# sistema_min.net
KiCad netlist of a schematic drawn in EAGLE
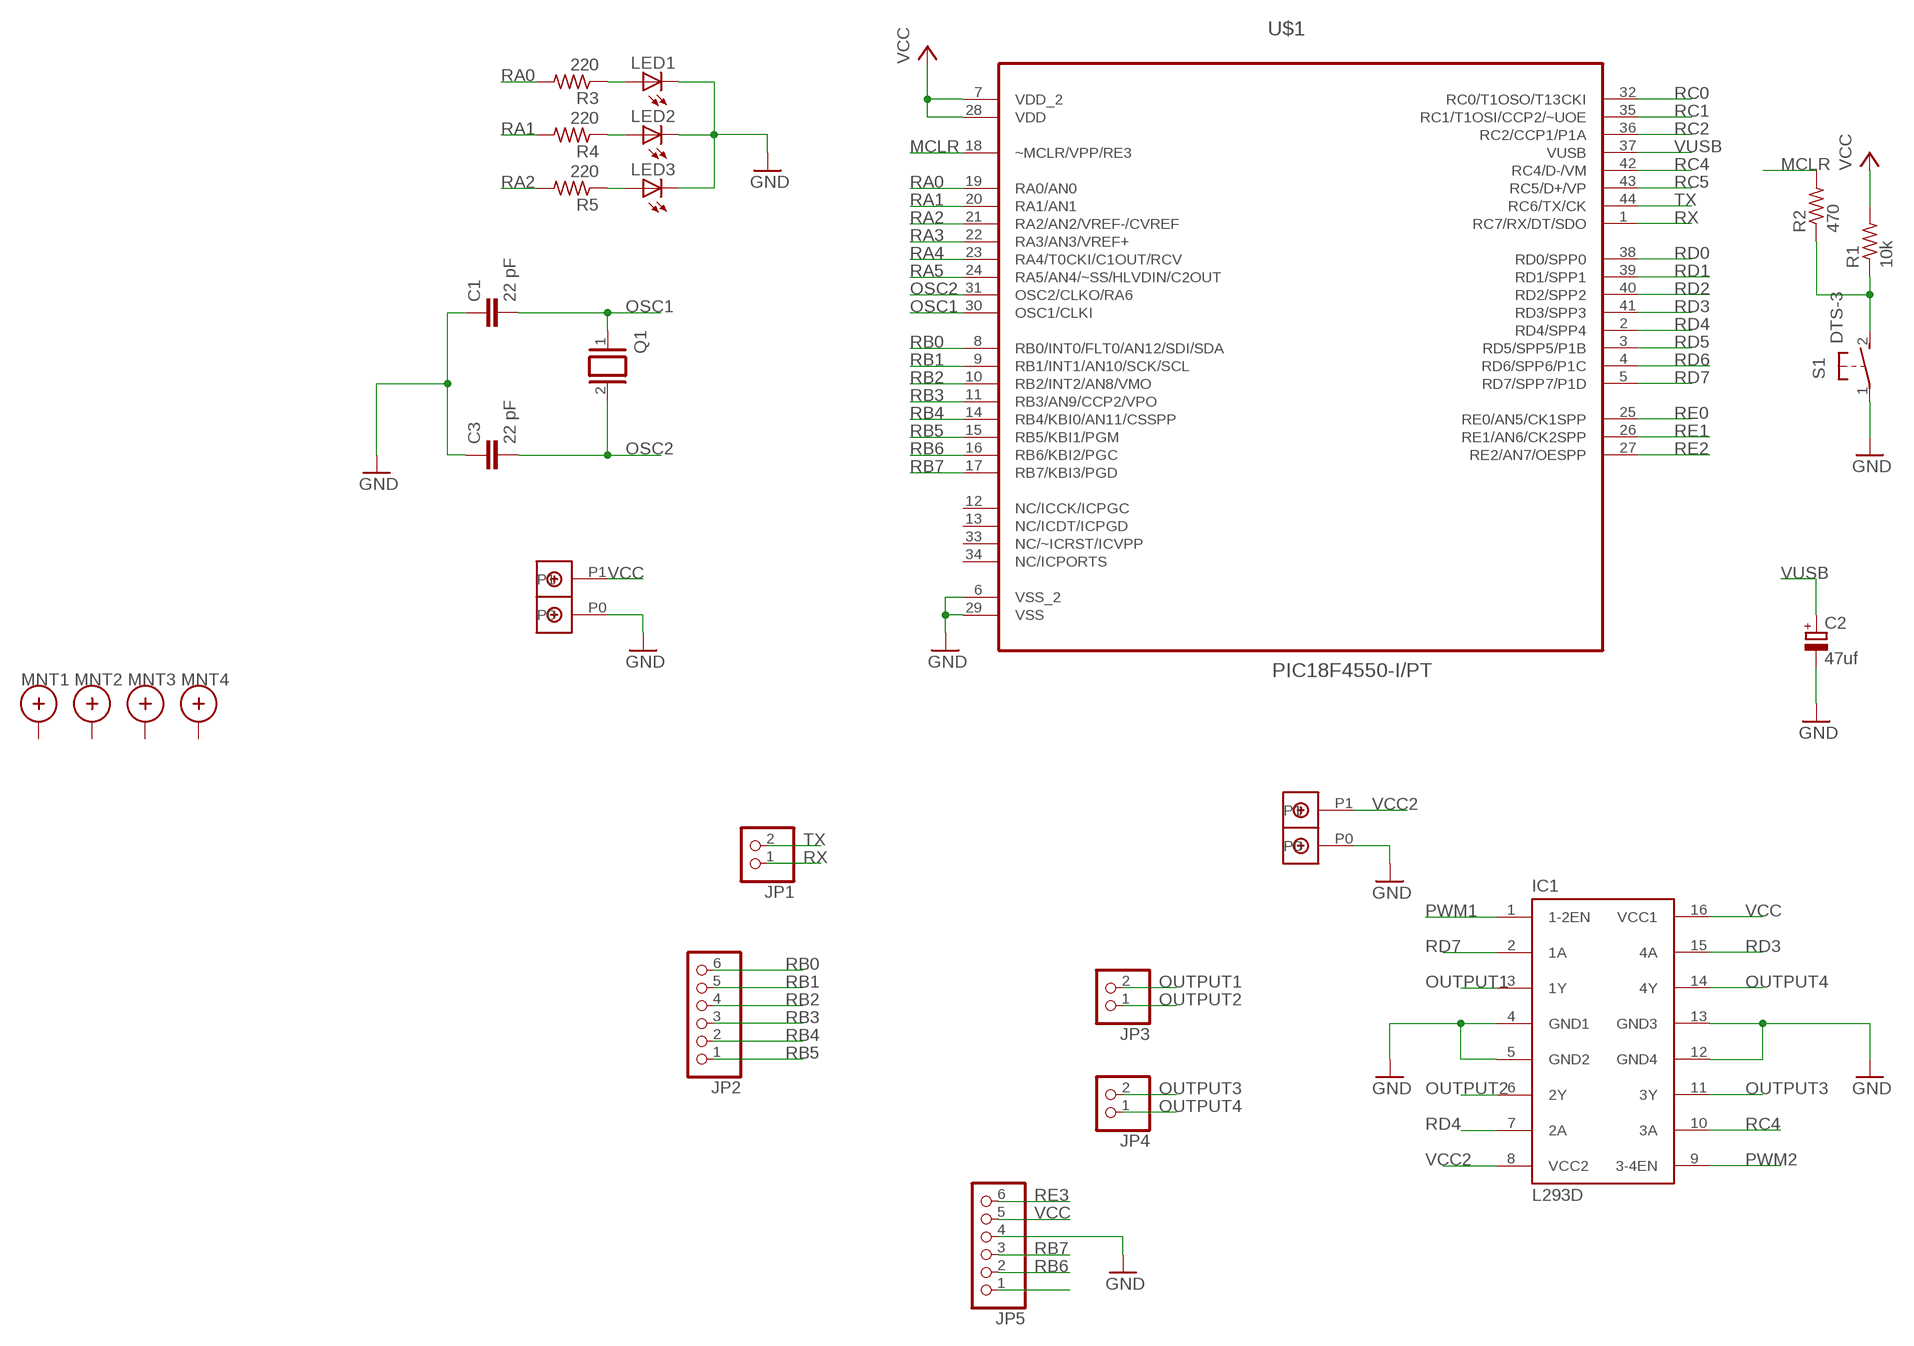
[diagram p0: schematic, sheet 1]

(export (version "E")
  (design (tool "Eeschema 10.0.6"))
  (components
    (comp (ref "C1")
      (value "22 pF")
      (footprint "eagle-import:C1206")
      (libsource (lib "eagle-import") (part "C-EUC1206"))
    )
    (comp (ref "C2")
      (value "47uf")
      (footprint "eagle-import:153CLV-0605")
      (libsource (lib "eagle-import") (part "CPOL-EU153CLV-0605"))
    )
    (comp (ref "C3")
      (value "22 pF")
      (footprint "eagle-import:C1206")
      (libsource (lib "eagle-import") (part "C-EUC1206"))
    )
    (comp (ref "IC1")
      (value "L293D")
      (footprint "eagle-import:DIL16")
      (libsource (lib "eagle-import") (part "L293D"))
    )
    (comp (ref "JP1")
      (value "PINHD-1X2")
      (footprint "eagle-import:1X02")
      (libsource (lib "eagle-import") (part "PINHD-1X2"))
    )
    (comp (ref "JP2")
      (value "PINHD-1X6")
      (footprint "eagle-import:1X06")
      (libsource (lib "eagle-import") (part "PINHD-1X6"))
    )
    (comp (ref "JP3")
      (value "PINHD-1X2")
      (footprint "eagle-import:1X02")
      (libsource (lib "eagle-import") (part "PINHD-1X2"))
    )
    (comp (ref "JP4")
      (value "PINHD-1X2")
      (footprint "eagle-import:1X02")
      (libsource (lib "eagle-import") (part "PINHD-1X2"))
    )
    (comp (ref "JP5")
      (value "PINHD-1X6")
      (footprint "eagle-import:1X06")
      (libsource (lib "eagle-import") (part "PINHD-1X6"))
    )
    (comp (ref "LED1")
      (value "LEDCHIPLED_1206")
      (footprint "eagle-import:CHIPLED_1206")
      (libsource (lib "eagle-import") (part "LEDCHIPLED_1206"))
    )
    (comp (ref "LED2")
      (value "LEDCHIPLED_1206")
      (footprint "eagle-import:CHIPLED_1206")
      (libsource (lib "eagle-import") (part "LEDCHIPLED_1206"))
    )
    (comp (ref "LED3")
      (value "LEDCHIPLED_1206")
      (footprint "eagle-import:CHIPLED_1206")
      (libsource (lib "eagle-import") (part "LEDCHIPLED_1206"))
    )
    (comp (ref "MNT1")
      (value "HOLE_MNT_0.135")
      (footprint "eagle-import:HOLE_MNT_#5-40")
      (libsource (lib "eagle-import") (part "HOLE_MNT_0.135"))
    )
    (comp (ref "MNT2")
      (value "HOLE_MNT_0.135")
      (footprint "eagle-import:HOLE_MNT_#5-40")
      (libsource (lib "eagle-import") (part "HOLE_MNT_0.135"))
    )
    (comp (ref "MNT3")
      (value "HOLE_MNT_0.135")
      (footprint "eagle-import:HOLE_MNT_#5-40")
      (libsource (lib "eagle-import") (part "HOLE_MNT_0.135"))
    )
    (comp (ref "MNT4")
      (value "HOLE_MNT_0.135")
      (footprint "eagle-import:HOLE_MNT_#5-40")
      (libsource (lib "eagle-import") (part "HOLE_MNT_0.135"))
    )
    (comp (ref "Q1")
      (value "XTAL/S")
      (footprint "eagle-import:QS")
      (libsource (lib "eagle-import") (part "XTAL/S"))
    )
    (comp (ref "R1")
      (value "10k")
      (footprint "eagle-import:M1206")
      (libsource (lib "eagle-import") (part "R-US_M1206"))
    )
    (comp (ref "R2")
      (value "470")
      (footprint "eagle-import:M1206")
      (libsource (lib "eagle-import") (part "R-US_M1206"))
    )
    (comp (ref "R3")
      (value "220")
      (footprint "eagle-import:M1206")
      (libsource (lib "eagle-import") (part "R-US_M1206"))
    )
    (comp (ref "R4")
      (value "220")
      (footprint "eagle-import:M1206")
      (libsource (lib "eagle-import") (part "R-US_M1206"))
    )
    (comp (ref "R5")
      (value "220")
      (footprint "eagle-import:M1206")
      (libsource (lib "eagle-import") (part "R-US_M1206"))
    )
    (comp (ref "S1")
      (value "DTS-3")
      (footprint "eagle-import:DTS-3")
      (libsource (lib "eagle-import") (part "DTS-3"))
    )
    (comp (ref "U$1")
      (value "PIC18F4550-I/PT")
      (footprint "eagle-import:QFP80P1200X1200X120-44N")
      (libsource (lib "eagle-import") (part "PIC18F4550-I/PT"))
    )
    (comp (ref "U$2")
      (value "DBCONN-1X2")
      (footprint "eagle-import:DBCONN-1X2")
      (libsource (lib "eagle-import") (part "DBCONN-1X2"))
    )
    (comp (ref "U$3")
      (value "DBCONN-1X2")
      (footprint "eagle-import:DBCONN-1X2")
      (libsource (lib "eagle-import") (part "DBCONN-1X2"))
    )
  )
  (nets
    (net (code "1") (name "/MCLR") (class "Default")
      (node (ref "R2") (pin "2") (pinfunction "2_2") (pintype "passive"))
      (node (ref "U$1") (pin "18") (pinfunction "~{MCLR/VPP/RE3}_18") (pintype "input"))
    )
    (net (code "2") (name "/OSC1") (class "Default")
      (node (ref "C1") (pin "2") (pinfunction "2_2") (pintype "passive"))
      (node (ref "Q1") (pin "1") (pinfunction "1_1") (pintype "passive"))
      (node (ref "U$1") (pin "30") (pinfunction "OSC1/CLKI_30") (pintype "bidirectional"))
    )
    (net (code "3") (name "/OSC2") (class "Default")
      (node (ref "C3") (pin "2") (pinfunction "2_2") (pintype "passive"))
      (node (ref "Q1") (pin "2") (pinfunction "2_2") (pintype "passive"))
      (node (ref "U$1") (pin "31") (pinfunction "OSC2/CLKO/RA6_31") (pintype "bidirectional"))
    )
    (net (code "4") (name "/OUTPUT1") (class "Default")
      (node (ref "IC1") (pin "3") (pinfunction "1Y_3") (pintype "output"))
      (node (ref "JP3") (pin "2") (pinfunction "2_2") (pintype "passive"))
    )
    (net (code "5") (name "/OUTPUT2") (class "Default")
      (node (ref "IC1") (pin "6") (pinfunction "2Y_6") (pintype "output"))
      (node (ref "JP3") (pin "1") (pinfunction "1_1") (pintype "passive"))
    )
    (net (code "6") (name "/OUTPUT3") (class "Default")
      (node (ref "IC1") (pin "11") (pinfunction "3Y_11") (pintype "output"))
      (node (ref "JP4") (pin "2") (pinfunction "2_2") (pintype "passive"))
    )
    (net (code "7") (name "/OUTPUT4") (class "Default")
      (node (ref "IC1") (pin "14") (pinfunction "4Y_14") (pintype "output"))
      (node (ref "JP4") (pin "1") (pinfunction "1_1") (pintype "passive"))
    )
    (net (code "8") (name "/PWM1") (class "Default")
      (node (ref "IC1") (pin "1") (pinfunction "1-2EN_1") (pintype "input"))
    )
    (net (code "9") (name "/PWM2") (class "Default")
      (node (ref "IC1") (pin "9") (pinfunction "3-4EN_9") (pintype "input"))
    )
    (net (code "10") (name "/RA0") (class "Default")
      (node (ref "R3") (pin "2") (pinfunction "2_2") (pintype "passive"))
      (node (ref "U$1") (pin "19") (pinfunction "RA0/AN0_19") (pintype "bidirectional"))
    )
    (net (code "11") (name "/RA1") (class "Default")
      (node (ref "R4") (pin "2") (pinfunction "2_2") (pintype "passive"))
      (node (ref "U$1") (pin "20") (pinfunction "RA1/AN1_20") (pintype "bidirectional"))
    )
    (net (code "12") (name "/RA2") (class "Default")
      (node (ref "R5") (pin "2") (pinfunction "2_2") (pintype "passive"))
      (node (ref "U$1") (pin "21") (pinfunction "RA2/AN2/VREF-/CVREF_21") (pintype "bidirectional"))
    )
    (net (code "13") (name "/RA3") (class "Default")
      (node (ref "U$1") (pin "22") (pinfunction "RA3/AN3/VREF+_22") (pintype "bidirectional"))
    )
    (net (code "14") (name "/RA4") (class "Default")
      (node (ref "U$1") (pin "23") (pinfunction "RA4/T0CKI/C1OUT/RCV_23") (pintype "bidirectional"))
    )
    (net (code "15") (name "/RA5") (class "Default")
      (node (ref "U$1") (pin "24") (pinfunction "RA5/AN4/~{SS/HLVDIN/C2OUT}_24") (pintype "bidirectional"))
    )
    (net (code "16") (name "/RB0") (class "Default")
      (node (ref "JP2") (pin "6") (pinfunction "6_6") (pintype "passive"))
      (node (ref "U$1") (pin "8") (pinfunction "RB0/INT0/FLT0/AN12/SDI/SDA_8") (pintype "bidirectional"))
    )
    (net (code "17") (name "/RB1") (class "Default")
      (node (ref "JP2") (pin "5") (pinfunction "5_5") (pintype "passive"))
      (node (ref "U$1") (pin "9") (pinfunction "RB1/INT1/AN10/SCK/SCL_9") (pintype "bidirectional"))
    )
    (net (code "18") (name "/RB2") (class "Default")
      (node (ref "JP2") (pin "4") (pinfunction "4_4") (pintype "passive"))
      (node (ref "U$1") (pin "10") (pinfunction "RB2/INT2/AN8/VMO_10") (pintype "bidirectional"))
    )
    (net (code "19") (name "/RB3") (class "Default")
      (node (ref "JP2") (pin "3") (pinfunction "3_3") (pintype "passive"))
      (node (ref "U$1") (pin "11") (pinfunction "RB3/AN9/CCP2/VPO_11") (pintype "bidirectional"))
    )
    (net (code "20") (name "/RB4") (class "Default")
      (node (ref "JP2") (pin "2") (pinfunction "2_2") (pintype "passive"))
      (node (ref "U$1") (pin "14") (pinfunction "RB4/KBI0/AN11/CSSPP_14") (pintype "bidirectional"))
    )
    (net (code "21") (name "/RB5") (class "Default")
      (node (ref "JP2") (pin "1") (pinfunction "1_1") (pintype "passive"))
      (node (ref "U$1") (pin "15") (pinfunction "RB5/KBI1/PGM_15") (pintype "bidirectional"))
    )
    (net (code "22") (name "/RB6") (class "Default")
      (node (ref "JP5") (pin "2") (pinfunction "2_2") (pintype "passive"))
      (node (ref "U$1") (pin "16") (pinfunction "RB6/KBI2/PGC_16") (pintype "bidirectional"))
    )
    (net (code "23") (name "/RB7") (class "Default")
      (node (ref "JP5") (pin "3") (pinfunction "3_3") (pintype "passive"))
      (node (ref "U$1") (pin "17") (pinfunction "RB7/KBI3/PGD_17") (pintype "bidirectional"))
    )
    (net (code "24") (name "/RC0") (class "Default")
      (node (ref "U$1") (pin "32") (pinfunction "RC0/T1OSO/T13CKI_32") (pintype "bidirectional"))
    )
    (net (code "25") (name "/RC1") (class "Default")
      (node (ref "U$1") (pin "35") (pinfunction "RC1/T1OSI/CCP2/~{UOE}_35") (pintype "bidirectional"))
    )
    (net (code "26") (name "/RC2") (class "Default")
      (node (ref "U$1") (pin "36") (pinfunction "RC2/CCP1/P1A_36") (pintype "bidirectional"))
    )
    (net (code "27") (name "/RC4") (class "Default")
      (node (ref "IC1") (pin "10") (pinfunction "3A_10") (pintype "input"))
      (node (ref "U$1") (pin "42") (pinfunction "RC4/D-/VM_42") (pintype "bidirectional"))
    )
    (net (code "28") (name "/RC5") (class "Default")
      (node (ref "U$1") (pin "43") (pinfunction "RC5/D+/VP_43") (pintype "bidirectional"))
    )
    (net (code "29") (name "/RD0") (class "Default")
      (node (ref "U$1") (pin "38") (pinfunction "RD0/SPP0_38") (pintype "bidirectional"))
    )
    (net (code "30") (name "/RD1") (class "Default")
      (node (ref "U$1") (pin "39") (pinfunction "RD1/SPP1_39") (pintype "bidirectional"))
    )
    (net (code "31") (name "/RD2") (class "Default")
      (node (ref "U$1") (pin "40") (pinfunction "RD2/SPP2_40") (pintype "bidirectional"))
    )
    (net (code "32") (name "/RD3") (class "Default")
      (node (ref "IC1") (pin "15") (pinfunction "4A_15") (pintype "input"))
      (node (ref "U$1") (pin "41") (pinfunction "RD3/SPP3_41") (pintype "bidirectional"))
    )
    (net (code "33") (name "/RD4") (class "Default")
      (node (ref "IC1") (pin "7") (pinfunction "2A_7") (pintype "input"))
      (node (ref "U$1") (pin "2") (pinfunction "RD4/SPP4_2") (pintype "bidirectional"))
    )
    (net (code "34") (name "/RD5") (class "Default")
      (node (ref "U$1") (pin "3") (pinfunction "RD5/SPP5/P1B_3") (pintype "bidirectional"))
    )
    (net (code "35") (name "/RD6") (class "Default")
      (node (ref "U$1") (pin "4") (pinfunction "RD6/SPP6/P1C_4") (pintype "bidirectional"))
    )
    (net (code "36") (name "/RD7") (class "Default")
      (node (ref "IC1") (pin "2") (pinfunction "1A_2") (pintype "input"))
      (node (ref "U$1") (pin "5") (pinfunction "RD7/SPP7/P1D_5") (pintype "bidirectional"))
    )
    (net (code "37") (name "/RE0") (class "Default")
      (node (ref "U$1") (pin "25") (pinfunction "RE0/AN5/CK1SPP_25") (pintype "bidirectional"))
    )
    (net (code "38") (name "/RE1") (class "Default")
      (node (ref "U$1") (pin "26") (pinfunction "RE1/AN6/CK2SPP_26") (pintype "bidirectional"))
    )
    (net (code "39") (name "/RE2") (class "Default")
      (node (ref "U$1") (pin "27") (pinfunction "RE2/AN7/OESPP_27") (pintype "bidirectional"))
    )
    (net (code "40") (name "/RE3") (class "Default")
      (node (ref "JP5") (pin "6") (pinfunction "6_6") (pintype "passive"))
    )
    (net (code "41") (name "/RX") (class "Default")
      (node (ref "JP1") (pin "1") (pinfunction "1_1") (pintype "passive"))
      (node (ref "U$1") (pin "1") (pinfunction "RC7/RX/DT/SDO_1") (pintype "bidirectional"))
    )
    (net (code "42") (name "/TX") (class "Default")
      (node (ref "JP1") (pin "2") (pinfunction "2_2") (pintype "passive"))
      (node (ref "U$1") (pin "44") (pinfunction "RC6/TX/CK_44") (pintype "bidirectional"))
    )
    (net (code "43") (name "/VCC2") (class "Default")
      (node (ref "IC1") (pin "8") (pinfunction "VCC2_8") (pintype "power_in"))
      (node (ref "U$3") (pin "P1") (pinfunction "P1_P1") (pintype "bidirectional"))
    )
    (net (code "44") (name "/VUSB") (class "Default")
      (node (ref "C2") (pin "+") (pinfunction "+_+") (pintype "passive"))
      (node (ref "U$1") (pin "37") (pinfunction "VUSB_37") (pintype "bidirectional"))
    )
    (net (code "45") (name "GND") (class "Default")
      (node (ref "C1") (pin "1") (pinfunction "1_1") (pintype "passive"))
      (node (ref "C2") (pin "-") (pinfunction "-_-") (pintype "passive"))
      (node (ref "C3") (pin "1") (pinfunction "1_1") (pintype "passive"))
      (node (ref "IC1") (pin "12") (pinfunction "GND4_12") (pintype "power_in"))
      (node (ref "IC1") (pin "13") (pinfunction "GND3_13") (pintype "power_in"))
      (node (ref "IC1") (pin "4") (pinfunction "GND1_4") (pintype "power_in"))
      (node (ref "IC1") (pin "5") (pinfunction "GND2_5") (pintype "power_in"))
      (node (ref "JP5") (pin "4") (pinfunction "4_4") (pintype "passive"))
      (node (ref "LED1") (pin "C") (pinfunction "C_C") (pintype "passive"))
      (node (ref "LED2") (pin "C") (pinfunction "C_C") (pintype "passive"))
      (node (ref "LED3") (pin "C") (pinfunction "C_C") (pintype "passive"))
      (node (ref "S1") (pin "1") (pinfunction "1_1") (pintype "passive"))
      (node (ref "U$1") (pin "29") (pinfunction "VSS_29") (pintype "power_in"))
      (node (ref "U$1") (pin "6") (pinfunction "VSS_2_6") (pintype "power_in"))
      (node (ref "U$2") (pin "P0") (pinfunction "P0_P0") (pintype "bidirectional"))
      (node (ref "U$3") (pin "P0") (pinfunction "P0_P0") (pintype "bidirectional"))
    )
    (net (code "46") (name "Net-(LED1-PadA)") (class "Default")
      (node (ref "LED1") (pin "A") (pinfunction "A_A") (pintype "passive"))
      (node (ref "R3") (pin "1") (pinfunction "1_1") (pintype "passive"))
    )
    (net (code "47") (name "Net-(LED2-PadA)") (class "Default")
      (node (ref "LED2") (pin "A") (pinfunction "A_A") (pintype "passive"))
      (node (ref "R4") (pin "1") (pinfunction "1_1") (pintype "passive"))
    )
    (net (code "48") (name "Net-(LED3-PadA)") (class "Default")
      (node (ref "LED3") (pin "A") (pinfunction "A_A") (pintype "passive"))
      (node (ref "R5") (pin "1") (pinfunction "1_1") (pintype "passive"))
    )
    (net (code "49") (name "Net-(R1-Pad1)") (class "Default")
      (node (ref "R1") (pin "1") (pinfunction "1_1") (pintype "passive"))
      (node (ref "R2") (pin "1") (pinfunction "1_1") (pintype "passive"))
      (node (ref "S1") (pin "2") (pinfunction "2_2") (pintype "passive"))
    )
    (net (code "50") (name "VCC") (class "Default")
      (node (ref "IC1") (pin "16") (pinfunction "VCC1_16") (pintype "power_in"))
      (node (ref "JP5") (pin "5") (pinfunction "5_5") (pintype "passive"))
      (node (ref "R1") (pin "2") (pinfunction "2_2") (pintype "passive"))
      (node (ref "U$1") (pin "28") (pinfunction "VDD_28") (pintype "power_in"))
      (node (ref "U$1") (pin "7") (pinfunction "VDD_2_7") (pintype "power_in"))
      (node (ref "U$2") (pin "P1") (pinfunction "P1_P1") (pintype "bidirectional"))
    )
    (net (code "51") (name "unconnected-(JP5-Pad1)") (class "Default")
      (node (ref "JP5") (pin "1") (pinfunction "1_1") (pintype "passive"))
    )
    (net (code "52") (name "unconnected-(MNT1-1-PadP$1)") (class "Default")
      (node (ref "MNT1") (pin "P$1") (pinfunction "1_P$1") (pintype "bidirectional"))
    )
    (net (code "53") (name "unconnected-(MNT2-1-PadP$1)") (class "Default")
      (node (ref "MNT2") (pin "P$1") (pinfunction "1_P$1") (pintype "bidirectional"))
    )
    (net (code "54") (name "unconnected-(MNT3-1-PadP$1)") (class "Default")
      (node (ref "MNT3") (pin "P$1") (pinfunction "1_P$1") (pintype "bidirectional"))
    )
    (net (code "55") (name "unconnected-(MNT4-1-PadP$1)") (class "Default")
      (node (ref "MNT4") (pin "P$1") (pinfunction "1_P$1") (pintype "bidirectional"))
    )
    (net (code "56") (name "unconnected-(U$1-NC{slash}ICCK{slash}ICPGC-Pad12)") (class "Default")
      (node (ref "U$1") (pin "12") (pinfunction "NC/ICCK/ICPGC_12") (pintype "no_connect"))
    )
    (net (code "57") (name "unconnected-(U$1-NC{slash}ICDT{slash}ICPGD-Pad13)") (class "Default")
      (node (ref "U$1") (pin "13") (pinfunction "NC/ICDT/ICPGD_13") (pintype "no_connect"))
    )
    (net (code "58") (name "unconnected-(U$1-NC{slash}ICPORTS-Pad34)") (class "Default")
      (node (ref "U$1") (pin "34") (pinfunction "NC/ICPORTS_34") (pintype "no_connect"))
    )
    (net (code "59") (name "unconnected-(U$1-NC{slash}~{ICRST{slash}ICVPP}-Pad33)") (class "Default")
      (node (ref "U$1") (pin "33") (pinfunction "NC/~{ICRST/ICVPP}_33") (pintype "no_connect"))
    )
  )
)
